# LM358_VCO.net
KiCad netlist of a schematic drawn in EAGLE
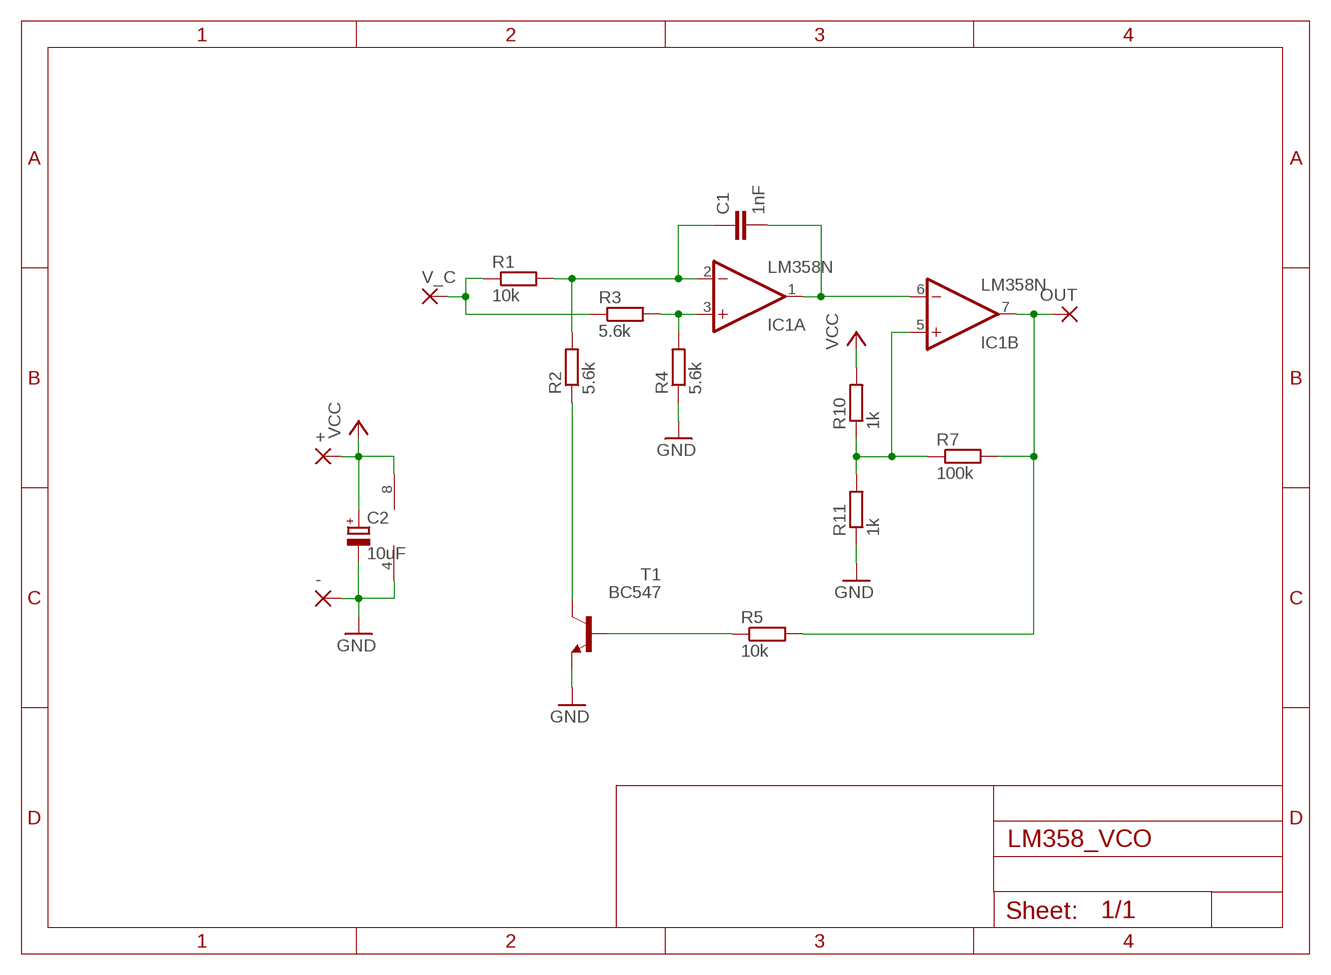
[diagram p0: schematic, sheet 1]

(export (version "E")
  (design (tool "Eeschema 10.0.6"))
  (components
    (comp (ref "+")
      (value "1,6/0,8")
      (footprint "eagle-import:1,6_0,8")
      (libsource (lib "eagle-import") (part "1,6/0,8"))
    )
    (comp (ref "-")
      (value "1,6/0,8")
      (footprint "eagle-import:1,6_0,8")
      (libsource (lib "eagle-import") (part "1,6/0,8"))
    )
    (comp (ref "C1")
      (value "1nF")
      (footprint "eagle-import:C050-025X075")
      (libsource (lib "eagle-import") (part "C-EU050-025X075"))
    )
    (comp (ref "C2")
      (value "10uF")
      (footprint "eagle-import:B45181A")
      (libsource (lib "eagle-import") (part "CPOL-EUB45181A"))
    )
    (comp (ref "IC1")
      (value "LM358N")
      (footprint "eagle-import:DIL08")
      (libsource (lib "eagle-import") (part "LM358N"))
    )
    (comp (ref "OUT")
      (value "1,6/0,8")
      (footprint "eagle-import:1,6_0,8")
      (libsource (lib "eagle-import") (part "1,6/0,8"))
    )
    (comp (ref "R1")
      (value "10k")
      (footprint "eagle-import:0204_7")
      (libsource (lib "eagle-import") (part "R-EU_0204/7"))
    )
    (comp (ref "R2")
      (value "5.6k")
      (footprint "eagle-import:0204_7")
      (libsource (lib "eagle-import") (part "R-EU_0204/7"))
    )
    (comp (ref "R3")
      (value "5.6k")
      (footprint "eagle-import:0204_7")
      (libsource (lib "eagle-import") (part "R-EU_0204/7"))
    )
    (comp (ref "R4")
      (value "5.6k")
      (footprint "eagle-import:0204_7")
      (libsource (lib "eagle-import") (part "R-EU_0204/7"))
    )
    (comp (ref "R5")
      (value "10k")
      (footprint "eagle-import:0204_7")
      (libsource (lib "eagle-import") (part "R-EU_0204/7"))
    )
    (comp (ref "R7")
      (value "100k")
      (footprint "eagle-import:0204_7")
      (libsource (lib "eagle-import") (part "R-EU_0204/7"))
    )
    (comp (ref "R10")
      (value "1k")
      (footprint "eagle-import:0204_7")
      (libsource (lib "eagle-import") (part "R-EU_0204/7"))
    )
    (comp (ref "R11")
      (value "1k")
      (footprint "eagle-import:0204_7")
      (libsource (lib "eagle-import") (part "R-EU_0204/7"))
    )
    (comp (ref "T1")
      (value "BC547")
      (footprint "eagle-import:TO92-CBE")
      (libsource (lib "eagle-import") (part "-NPN-TO92-CBEBC547"))
    )
    (comp (ref "V_C")
      (value "1,6/0,8")
      (footprint "eagle-import:1,6_0,8")
      (libsource (lib "eagle-import") (part "1,6/0,8"))
    )
  )
  (nets
    (net (code "1") (name "GND") (class "Default")
      (node (ref "-") (pin "1") (pinfunction "P_1") (pintype "passive"))
      (node (ref "C2") (pin "-") (pinfunction "-_-") (pintype "passive"))
      (node (ref "IC1") (pin "4") (pinfunction "V-_4") (pintype "power_in"))
      (node (ref "R11") (pin "1") (pinfunction "1_1") (pintype "passive"))
      (node (ref "R4") (pin "1") (pinfunction "1_1") (pintype "passive"))
      (node (ref "T1") (pin "E") (pinfunction "E_E") (pintype "passive"))
    )
    (net (code "2") (name "Net-(IC1A-+IN)") (class "Default")
      (node (ref "IC1") (pin "3") (pinfunction "+IN_3") (pintype "input"))
      (node (ref "R3") (pin "2") (pinfunction "2_2") (pintype "passive"))
      (node (ref "R4") (pin "2") (pinfunction "2_2") (pintype "passive"))
    )
    (net (code "3") (name "Net-(IC1A--IN)") (class "Default")
      (node (ref "C1") (pin "1") (pinfunction "1_1") (pintype "passive"))
      (node (ref "IC1") (pin "2") (pinfunction "-IN_2") (pintype "input"))
      (node (ref "R1") (pin "2") (pinfunction "2_2") (pintype "passive"))
      (node (ref "R2") (pin "2") (pinfunction "2_2") (pintype "passive"))
    )
    (net (code "4") (name "Net-(IC1A-OUT)") (class "Default")
      (node (ref "C1") (pin "2") (pinfunction "2_2") (pintype "passive"))
      (node (ref "IC1") (pin "1") (pinfunction "OUT_1") (pintype "output"))
      (node (ref "IC1") (pin "6") (pinfunction "-IN_6") (pintype "input"))
    )
    (net (code "5") (name "Net-(IC1B-+IN)") (class "Default")
      (node (ref "IC1") (pin "5") (pinfunction "+IN_5") (pintype "input"))
      (node (ref "R10") (pin "1") (pinfunction "1_1") (pintype "passive"))
      (node (ref "R11") (pin "2") (pinfunction "2_2") (pintype "passive"))
      (node (ref "R7") (pin "1") (pinfunction "1_1") (pintype "passive"))
    )
    (net (code "6") (name "Net-(IC1B-OUT)") (class "Default")
      (node (ref "IC1") (pin "7") (pinfunction "OUT_7") (pintype "output"))
      (node (ref "OUT") (pin "1") (pinfunction "P_1") (pintype "passive"))
      (node (ref "R5") (pin "2") (pinfunction "2_2") (pintype "passive"))
      (node (ref "R7") (pin "2") (pinfunction "2_2") (pintype "passive"))
    )
    (net (code "7") (name "Net-(R2-Pad1)") (class "Default")
      (node (ref "R2") (pin "1") (pinfunction "1_1") (pintype "passive"))
      (node (ref "T1") (pin "C") (pinfunction "C_C") (pintype "passive"))
    )
    (net (code "8") (name "Net-(R5-Pad1)") (class "Default")
      (node (ref "R5") (pin "1") (pinfunction "1_1") (pintype "passive"))
      (node (ref "T1") (pin "B") (pinfunction "B_B") (pintype "passive"))
    )
    (net (code "9") (name "Net-(V_C-P)") (class "Default")
      (node (ref "R1") (pin "1") (pinfunction "1_1") (pintype "passive"))
      (node (ref "R3") (pin "1") (pinfunction "1_1") (pintype "passive"))
      (node (ref "V_C") (pin "1") (pinfunction "P_1") (pintype "passive"))
    )
    (net (code "10") (name "VCC") (class "Default")
      (node (ref "+") (pin "1") (pinfunction "P_1") (pintype "passive"))
      (node (ref "C2") (pin "+") (pinfunction "+_+") (pintype "passive"))
      (node (ref "IC1") (pin "8") (pinfunction "V+_8") (pintype "power_in"))
      (node (ref "R10") (pin "2") (pinfunction "2_2") (pintype "passive"))
    )
  )
)
